# TSAL.net
KiCad netlist of a schematic drawn in Altium Designer
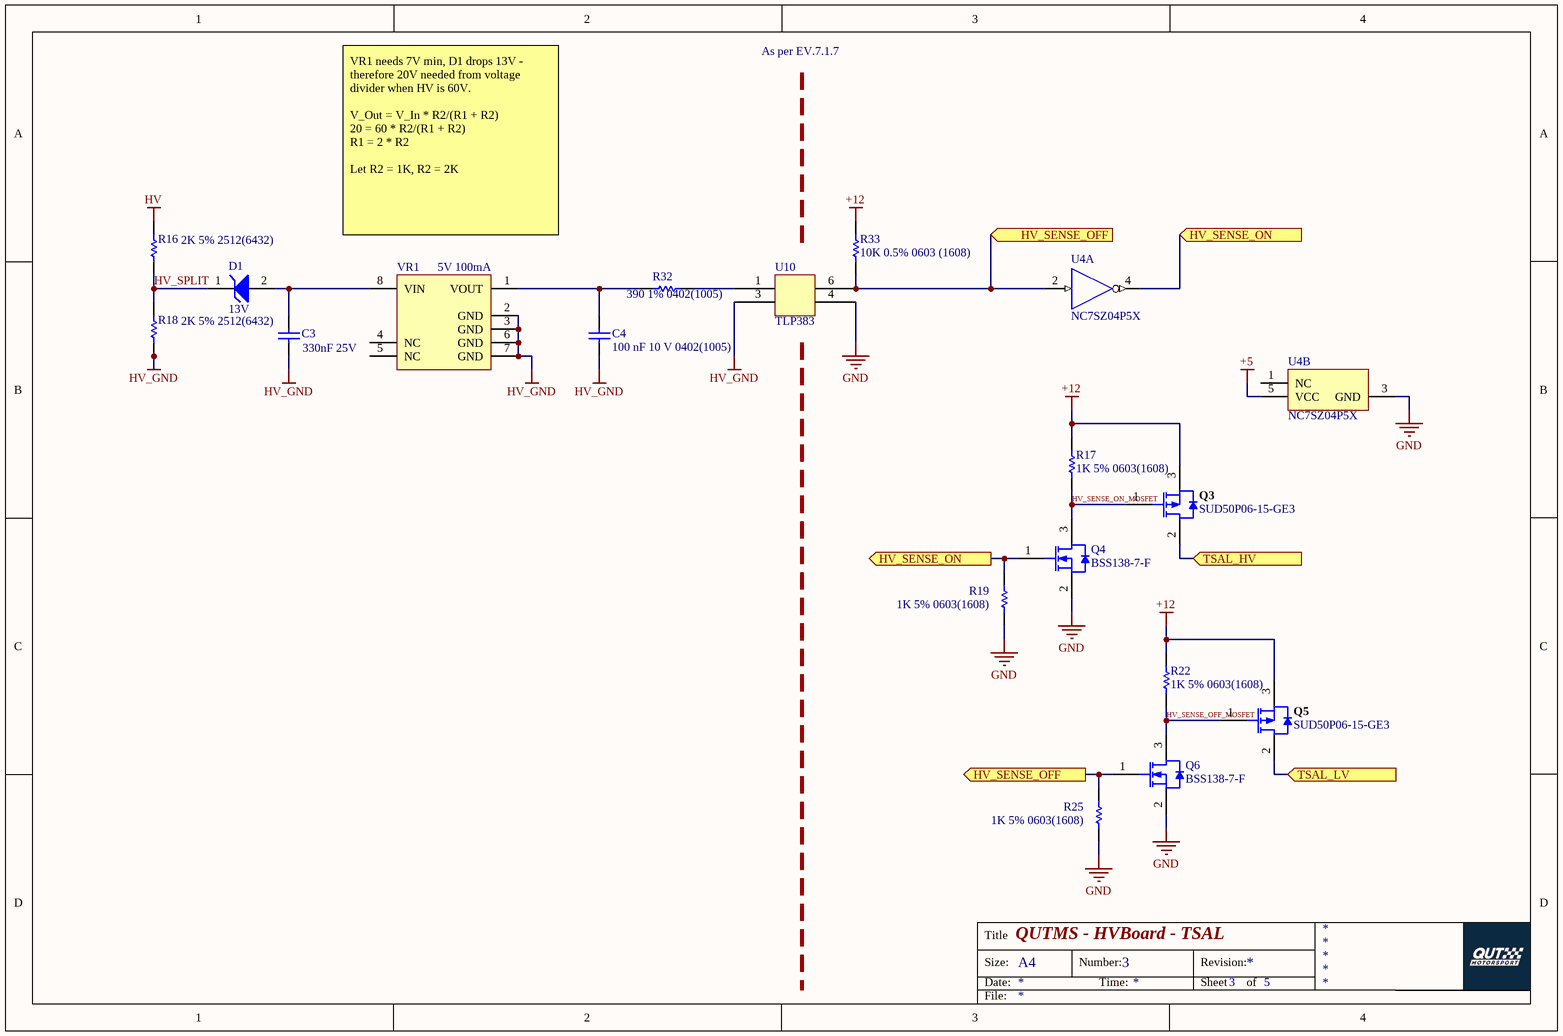
[diagram p0: TSAL.SchDoc]

(export (version "E")
  (design (tool "Eeschema 10.0.6"))
  (components
    (comp (ref "C3")
      (value "330nF 25V")
      (footprint "CAPC0603(1608)100_M")
      (description "CAP 330nF 25V ±20% 0603 (1608 Metric) Thickness 1mm SMD")
      (fields (field (name "TOLERANCE") "Â±20%"))
      (libsource (lib "Altium Content Vault") (part "CAP"))
    )
    (comp (ref "C4")
      (value "100 nF 10 V 0402(1005)")
      (footprint "CAPC1005X60X30ML05T10")
      (fields (field (name "PART NUMBER") "C0402C104K8PAC7867") (field (name "MANUFACTURER") "Kemet"))
      (libsource (lib "Altium Content Vault") (part "CAP"))
    )
    (comp (ref "D1")
      (value "13V")
      (footprint "ONSC-SOD-323-2-477-02_V")
      (description "Zener Voltage Regulator, 300 mW, Tight Tolerance Portfolio, 2-Pin SOD-323, Pb-Free, Tape and Reel")
      (fields (field (name "PARTNUMBER") "MM3Z13VT1G") (field (name "MANUFACTURER") "On Semiconductor"))
      (libsource (lib "Altium Content Vault") (part "ONSC-K1A2-2"))
    )
    (comp (ref "Q3")
      (value "SUD50P06-15-GE3")
      (footprint "VSIL-TO-252AA-3_V")
      (description "P-Channel (D-S) MOSFET, 30 V, -55 to 150 degC, 3-Pin TO-252, RoHS, Tape and Reel")
      (fields (field (name "MANUFACTURER") "Vishay"))
      (libsource (lib "Altium Content Vault") (part "PEMOS-GDS-3"))
    )
    (comp (ref "Q4")
      (value "BSS138-7-F")
      (footprint "DIOD-SOT23-3_V")
      (description "N-Channel Enhancement Mode Mosfet, 50 V, 0.2 A, -55 to 150 degC, 3-Pin SOT23, RoHS, Tape and Reel")
      (fields (field (name "MANUFACTURER") "Diodes Inc"))
      (libsource (lib "Altium Content Vault") (part "NEMOS-GSD-3"))
    )
    (comp (ref "Q5")
      (value "SUD50P06-15-GE3")
      (footprint "VSIL-TO-252AA-3_V")
      (description "P-Channel (D-S) MOSFET, 30 V, -55 to 150 degC, 3-Pin TO-252, RoHS, Tape and Reel")
      (fields (field (name "MANUFACTURER") "Vishay"))
      (libsource (lib "Altium Content Vault") (part "PEMOS-GDS-3"))
    )
    (comp (ref "Q6")
      (value "BSS138-7-F")
      (footprint "DIOD-SOT23-3_V")
      (description "N-Channel Enhancement Mode Mosfet, 50 V, 0.2 A, -55 to 150 degC, 3-Pin SOT23, RoHS, Tape and Reel")
      (fields (field (name "MANUFACTURER") "Diodes Inc"))
      (libsource (lib "Altium Content Vault") (part "NEMOS-GSD-3"))
    )
    (comp (ref "R16")
      (value "2K 5% 2512(6432)")
      (footprint "RESC2512(6432)_L")
      (description "2K 1W 5% 2512 (6432 Metric)  SMD")
      (fields (field (name "POWER") "1 W") (field (name "TOLERANCE") "5 %"))
      (libsource (lib "Altium Content Vault") (part "RES"))
    )
    (comp (ref "R17")
      (value "1K 5% 0603(1608)")
      (footprint "RESC0603(1608)_L")
      (description "1K 0.1W 5% 0603 (1608 Metric)  SMD")
      (fields (field (name "TOLERANCE") "5 %") (field (name "POWER") "0.1 W"))
      (libsource (lib "Altium Content Vault") (part "RES"))
    )
    (comp (ref "R18")
      (value "2K 5% 2512(6432)")
      (footprint "RESC2512(6432)_L")
      (description "2K 1W 5% 2512 (6432 Metric)  SMD")
      (fields (field (name "POWER") "1 W") (field (name "TOLERANCE") "5 %"))
      (libsource (lib "Altium Content Vault") (part "RES"))
    )
    (comp (ref "R19")
      (value "1K 5% 0603(1608)")
      (footprint "RESC0603(1608)_L")
      (description "1K 0.1W 5% 0603 (1608 Metric)  SMD")
      (fields (field (name "TOLERANCE") "5 %") (field (name "POWER") "0.1 W"))
      (libsource (lib "Altium Content Vault") (part "RES"))
    )
    (comp (ref "R22")
      (value "1K 5% 0603(1608)")
      (footprint "RESC0603(1608)_L")
      (description "1K 0.1W 5% 0603 (1608 Metric)  SMD")
      (fields (field (name "TOLERANCE") "5 %") (field (name "POWER") "0.1 W"))
      (libsource (lib "Altium Content Vault") (part "RES"))
    )
    (comp (ref "R25")
      (value "1K 5% 0603(1608)")
      (footprint "RESC0603(1608)_L")
      (description "1K 0.1W 5% 0603 (1608 Metric)  SMD")
      (fields (field (name "TOLERANCE") "5 %") (field (name "POWER") "0.1 W"))
      (libsource (lib "Altium Content Vault") (part "RES"))
    )
    (comp (ref "R32")
      (value "390 1% 0402(1005)")
      (footprint "RESC1609X50X30NL10T20")
      (fields (field (name "MANUFACTURER") "Vishay Dale") (field (name "PART NUMBER") "CRCW0603360RFKEA"))
      (libsource (lib "Altium Content Vault") (part "RES"))
    )
    (comp (ref "R33")
      (value "10K 0.5% 0603 (1608)")
      (footprint "RESC1608X50X30LL20T20")
      (fields (field (name "PART NUMBER") "RR0816P-103-D") (field (name "MANUFACTURER") "Susumu"))
      (libsource (lib "Altium Content Vault") (part "RES"))
    )
    (comp (ref "U4")
      (value "NC7SZ04P5X")
      (footprint "FAIR-SC70-5_V")
      (fields (field (name "MANUFACTURER") "FairchildSemiconductor"))
      (libsource (lib "Altium Content Vault") (part "FAIR-NC7SX04-5"))
    )
    (comp (ref "U10")
      (value "TLP383")
      (footprint "TLP383")
      (libsource (lib "QUTMS_OptoIsolatorLibrary") (part "TLP383"))
    )
    (comp (ref "VR1")
      (value "5V 100mA")
      (footprint "SO8_N")
      (description "Positive Voltage Regulator, 5V, 8-Pin SO, Tape and Reel")
      (libsource (lib "Altium Content Vault") (part "PM-REG-7805-IL8"))
    )
  )
  (nets
    (net (code "1") (name "+5") (class "Default")
      (node (ref "U4") (pin "5") (pinfunction "VCC_5") (pintype "power_in"))
    )
    (net (code "2") (name "+12") (class "Default")
      (node (ref "Q3") (pin "3") (pinfunction "S_3") (pintype "passive"))
      (node (ref "Q5") (pin "3") (pinfunction "S_3") (pintype "passive"))
      (node (ref "R17") (pin "2") (pinfunction "2_2") (pintype "passive"))
      (node (ref "R22") (pin "2") (pinfunction "2_2") (pintype "passive"))
      (node (ref "R33") (pin "2") (pinfunction "2_2") (pintype "passive"))
    )
    (net (code "3") (name "/HV_SENSE_OFF") (class "Default")
      (node (ref "Q6") (pin "1") (pinfunction "G_1") (pintype "passive"))
      (node (ref "R25") (pin "2") (pinfunction "2_2") (pintype "passive"))
      (node (ref "R33") (pin "1") (pinfunction "1_1") (pintype "passive"))
      (node (ref "U10") (pin "6") (pintype "power_in"))
      (node (ref "U4") (pin "2") (pinfunction "A_2") (pintype "input"))
    )
    (net (code "4") (name "/HV_SENSE_OFF_MOSFET") (class "Default")
      (node (ref "Q5") (pin "1") (pinfunction "G_1") (pintype "passive"))
      (node (ref "Q6") (pin "3") (pinfunction "D_3") (pintype "passive"))
      (node (ref "R22") (pin "1") (pinfunction "1_1") (pintype "passive"))
    )
    (net (code "5") (name "/HV_SENSE_ON") (class "Default")
      (node (ref "Q4") (pin "1") (pinfunction "G_1") (pintype "passive"))
      (node (ref "R19") (pin "2") (pinfunction "2_2") (pintype "passive"))
      (node (ref "U4") (pin "4") (pinfunction "Y_4") (pintype "output"))
    )
    (net (code "6") (name "/HV_SENSE_ON_MOSFET") (class "Default")
      (node (ref "Q3") (pin "1") (pinfunction "G_1") (pintype "passive"))
      (node (ref "Q4") (pin "3") (pinfunction "D_3") (pintype "passive"))
      (node (ref "R17") (pin "1") (pinfunction "1_1") (pintype "passive"))
    )
    (net (code "7") (name "/HV_SPLIT") (class "Default")
      (node (ref "D1") (pin "1") (pinfunction "K_1") (pintype "passive"))
      (node (ref "R16") (pin "1") (pinfunction "1_1") (pintype "passive"))
      (node (ref "R18") (pin "2") (pinfunction "2_2") (pintype "passive"))
    )
    (net (code "8") (name "/TSAL_HV") (class "Default")
      (node (ref "Q3") (pin "2") (pinfunction "D_2") (pintype "passive"))
    )
    (net (code "9") (name "/TSAL_LV") (class "Default")
      (node (ref "Q5") (pin "2") (pinfunction "D_2") (pintype "passive"))
    )
    (net (code "10") (name "GND") (class "Default")
      (node (ref "Q4") (pin "2") (pinfunction "S_2") (pintype "passive"))
      (node (ref "Q6") (pin "2") (pinfunction "S_2") (pintype "passive"))
      (node (ref "R19") (pin "1") (pinfunction "1_1") (pintype "passive"))
      (node (ref "R25") (pin "1") (pinfunction "1_1") (pintype "passive"))
      (node (ref "U10") (pin "4") (pintype "power_in"))
      (node (ref "U4") (pin "3") (pinfunction "GND_3") (pintype "power_in"))
    )
    (net (code "11") (name "HV") (class "Default")
      (node (ref "R16") (pin "2") (pinfunction "2_2") (pintype "passive"))
    )
    (net (code "12") (name "HV_GND") (class "Default")
      (node (ref "C3") (pin "1") (pinfunction "1_1") (pintype "passive"))
      (node (ref "C4") (pin "1") (pinfunction "1_1") (pintype "passive"))
      (node (ref "R18") (pin "1") (pinfunction "1_1") (pintype "passive"))
      (node (ref "U10") (pin "3") (pintype "power_in"))
      (node (ref "VR1") (pin "2") (pinfunction "GND_2") (pintype "power_in"))
      (node (ref "VR1") (pin "3") (pinfunction "GND_3") (pintype "power_in"))
      (node (ref "VR1") (pin "6") (pinfunction "GND_6") (pintype "power_in"))
      (node (ref "VR1") (pin "7") (pinfunction "GND_7") (pintype "power_in"))
    )
    (net (code "13") (name "Net-(D1-A)") (class "Default")
      (node (ref "C3") (pin "2") (pinfunction "2_2") (pintype "passive"))
      (node (ref "D1") (pin "2") (pinfunction "A_2") (pintype "passive"))
      (node (ref "VR1") (pin "8") (pinfunction "VIN_8") (pintype "power_in"))
    )
    (net (code "14") (name "Net-(R32-Pad2)") (class "Default")
      (node (ref "R32") (pin "2") (pinfunction "2_2") (pintype "passive"))
      (node (ref "U10") (pin "1") (pintype "power_in"))
    )
    (net (code "15") (name "Net-(VR1-VOUT)") (class "Default")
      (node (ref "C4") (pin "2") (pinfunction "2_2") (pintype "passive"))
      (node (ref "R32") (pin "1") (pinfunction "1_1") (pintype "passive"))
      (node (ref "VR1") (pin "1") (pinfunction "VOUT_1") (pintype "power_in"))
    )
    (net (code "16") (name "unconnected-(U4B-NC-Pad1)") (class "Default")
      (node (ref "U4") (pin "1") (pinfunction "NC_1") (pintype "power_in"))
    )
    (net (code "17") (name "unconnected-(VR1-NC-Pad4)") (class "Default")
      (node (ref "VR1") (pin "4") (pinfunction "NC_4") (pintype "passive"))
    )
    (net (code "18") (name "unconnected-(VR1-NC-Pad5)") (class "Default")
      (node (ref "VR1") (pin "5") (pinfunction "NC_5") (pintype "passive"))
    )
  )
)
